# MCU042A_Engine.net
KiCad netlist of a schematic drawn in Altium Designer
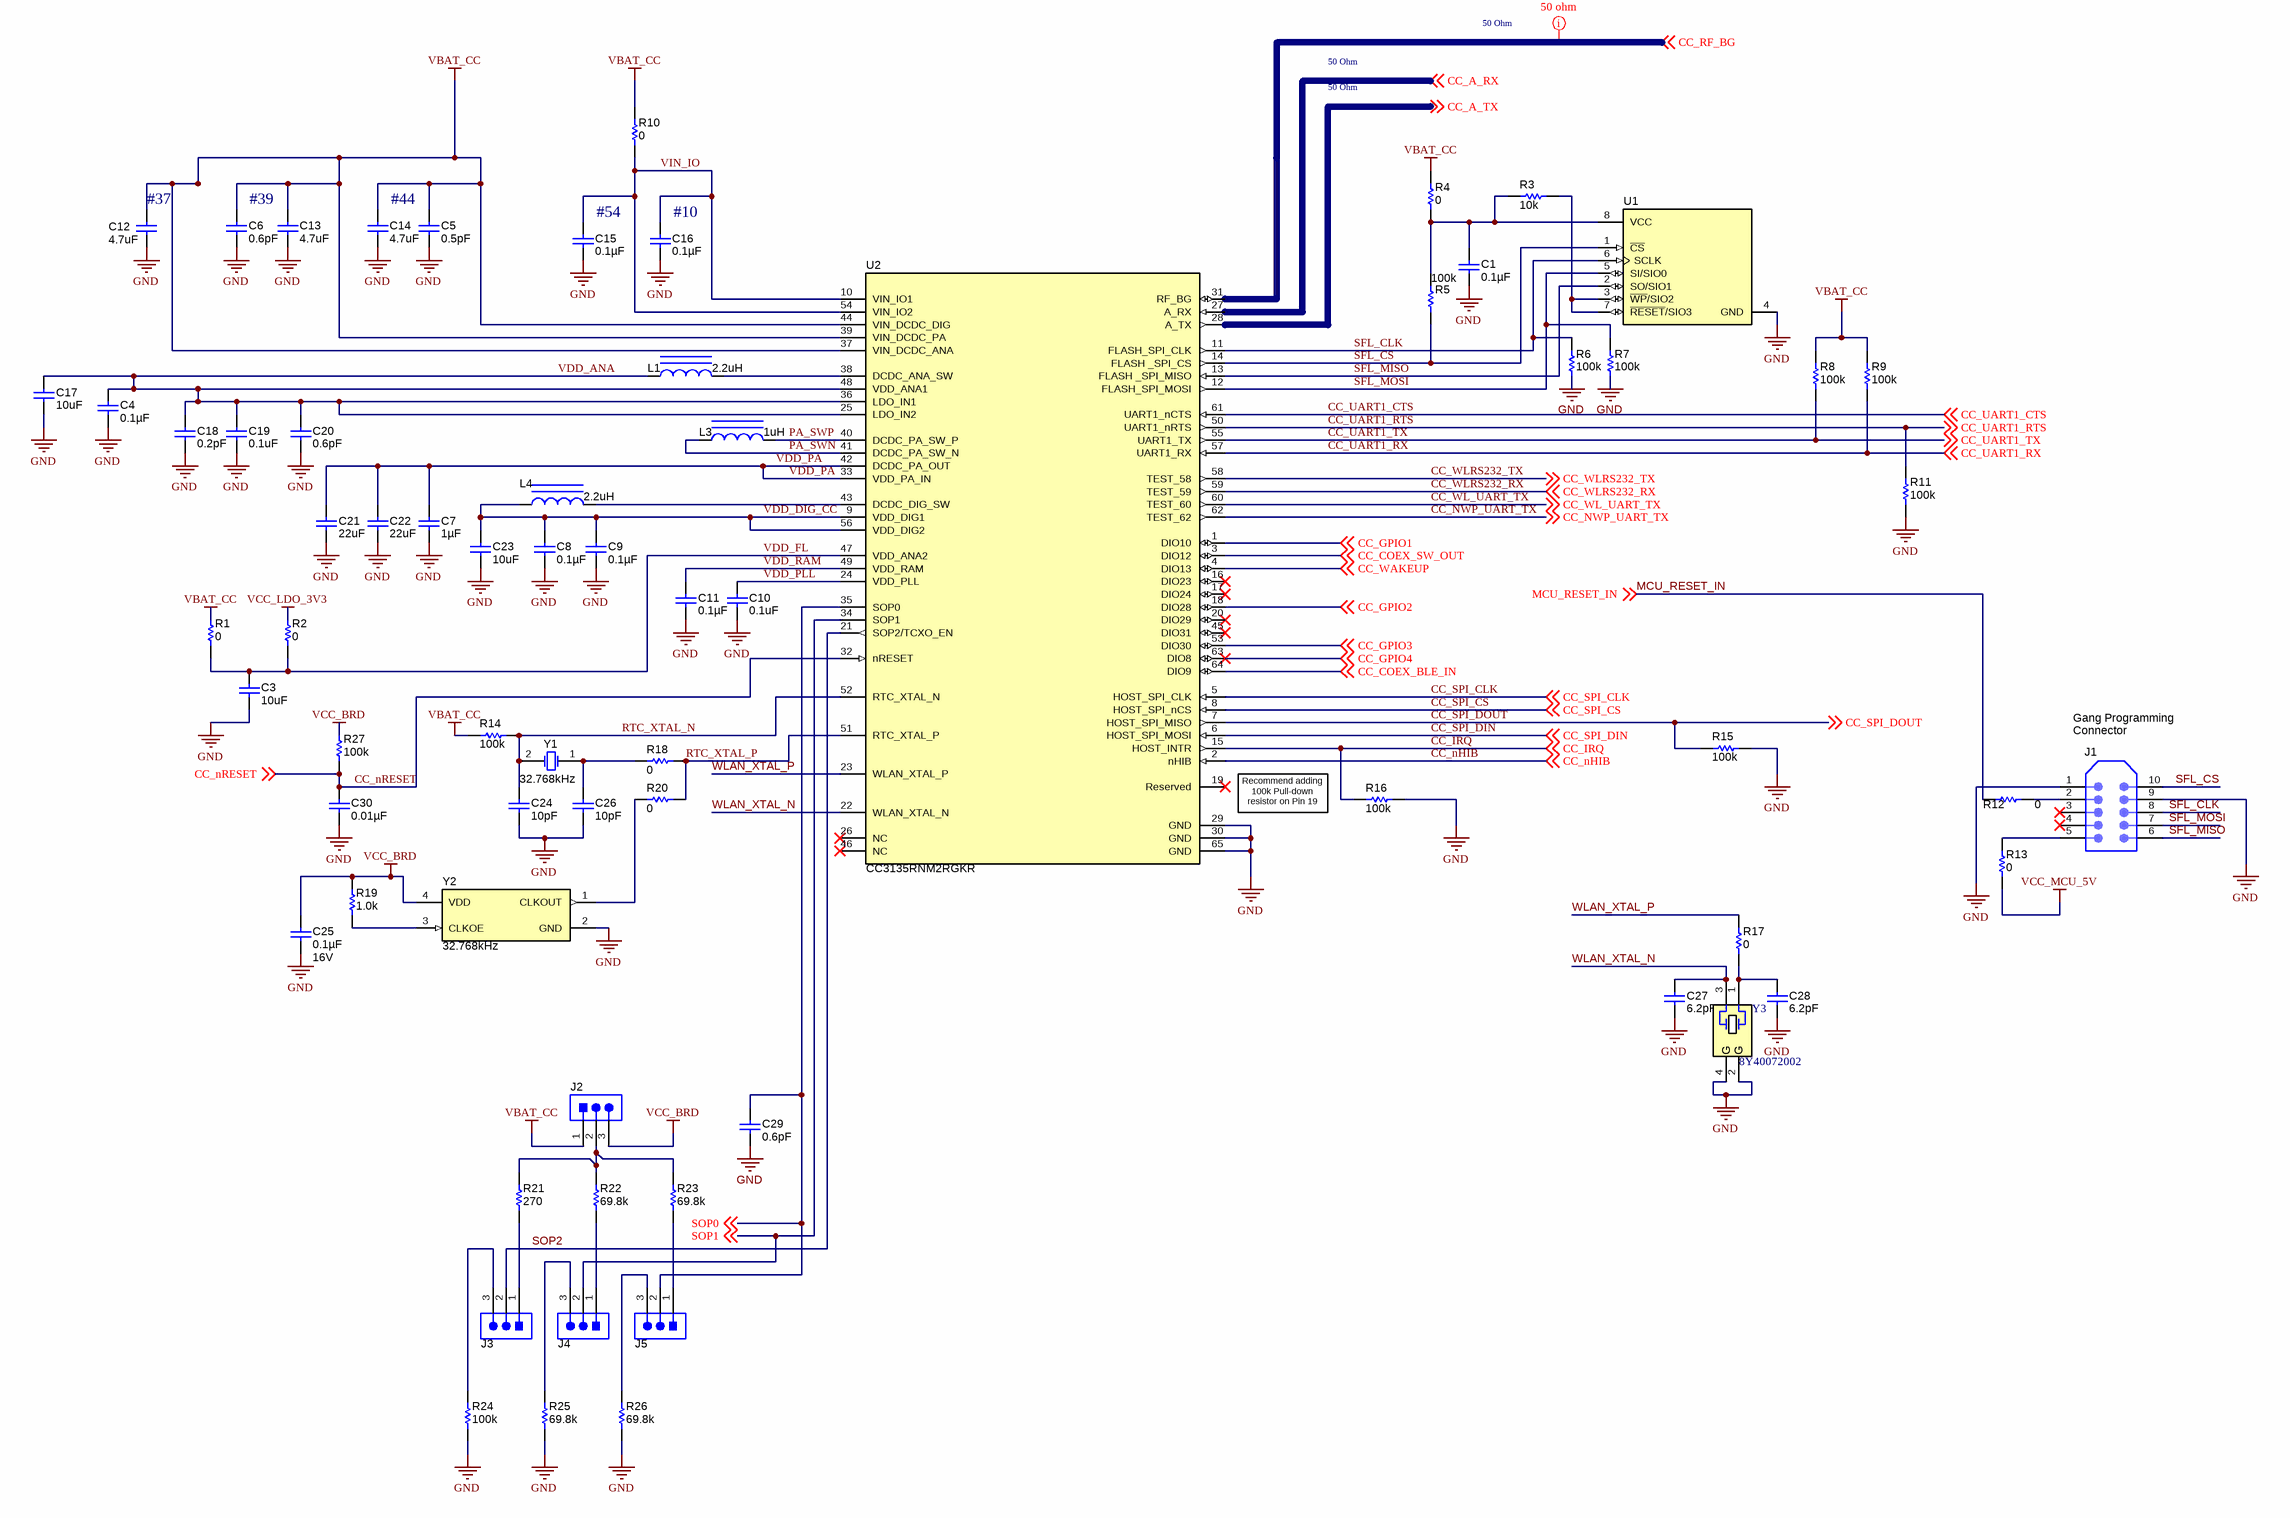
[diagram p0: MCU042A_Engine.SchDoc]

(export (version "E")
  (design (tool "Eeschema 10.0.6"))
  (components
    (comp (ref "C1")
      (value "CL05B104KO5NNNC")
      (footprint "0402")
      (description "CAP, CERM, 0.1 µF, 16 V,+/- 10%, X7R, 0402")
      (fields
        (field (name "VALUEDISPLAYED") "0.1µF")
        (field (name "MANUFACTURER") "Walsin")
        (field (name "ALTERNATE PARTNUMBER") "C1005X5R1A104K050BA")
      )
      (libsource (lib "Altium Vault - TI") (part "Capacitor"))
    )
    (comp (ref "C3")
      (value "CMP-0007303-5")
      (footprint "0603")
      (description "CAP, CERM, 10 uF, 6.3 V, +/- 20%, X5R, 0603")
      (fields
        (field (name "PARTNUMBER") "GRM188R60J106ME47D")
        (field (name "VALUEDISPLAYED") "10uF")
        (field (name "MANUFACTURER") "MuRata")
        (field (name "PUBLISHER") "Texas Instruments")
      )
      (libsource (lib "Altium Vault - TI") (part "CMP-0007303-5"))
    )
    (comp (ref "C4")
      (value "CL05B104KO5NNNC")
      (footprint "0402")
      (description "CAP, CERM, 0.1 µF, 16 V,+/- 10%, X7R, 0402")
      (fields
        (field (name "VALUEDISPLAYED") "0.1µF")
        (field (name "MANUFACTURER") "Walsin")
        (field (name "ALTERNATE PARTNUMBER") "C1005X5R1A104K050BA")
      )
      (libsource (lib "Altium Vault - TI") (part "Capacitor"))
    )
    (comp (ref "C5")
      (value "GJM0335C1ER50BB01D")
      (footprint "0201_033")
      (description "CAP, CERM, 0.5 pF, 25 V,+/- 20%, C0G/NP0, 0201")
      (fields (field (name "VALUEDISPLAYED") "0.5pF") (field (name "MANUFACTURER") "MuRata"))
      (libsource (lib "Altium Vault - TI") (part "Capacitor"))
    )
    (comp (ref "C6")
      (value "GJM0335C1ER60BB01D")
      (footprint "0201_033")
      (description "CAP, CERM, 0.6pF, 25 V,+/- 16%, C0G/NP0, 0201")
      (fields (field (name "VALUEDISPLAYED") "0.6pF") (field (name "MANUFACTURER") "MuRata"))
      (libsource (lib "Altium Vault - TI") (part "Capacitor"))
    )
    (comp (ref "C7")
      (value "CL05A105MP5NNNC")
      (footprint "0402")
      (description "CAP, CERM, 1 µF, 10 V,+/- 20%, X5R, 0402")
      (fields
        (field (name "VALUEDISPLAYED") "1µF")
        (field (name "MANUFACTURER") "Walsin")
        (field (name "ALTERNATE PARTNUMBER") "GRM155C81A105KA12D")
      )
      (libsource (lib "Altium Vault - TI") (part "Capacitor"))
    )
    (comp (ref "C8")
      (value "CL05B104KO5NNNC")
      (footprint "0402S")
      (description "CAP, CERM, 0.1 µF, 16 V,+/- 10%, X7R, 0402")
      (fields
        (field (name "VALUEDISPLAYED") "0.1µF")
        (field (name "MANUFACTURER") "Walsin")
        (field (name "ALTERNATE PARTNUMBER") "C1005X5R1A104K050BA")
      )
      (libsource (lib "Altium Vault - TI") (part "Capacitor"))
    )
    (comp (ref "C9")
      (value "CL05B104KO5NNNC")
      (footprint "0402S")
      (description "CAP, CERM, 0.1 µF, 16 V,+/- 10%, X7R, 0402")
      (fields
        (field (name "VALUEDISPLAYED") "0.1µF")
        (field (name "MANUFACTURER") "Walsin")
        (field (name "ALTERNATE PARTNUMBER") "C1005X5R1A104K050BA")
      )
      (libsource (lib "Altium Vault - TI") (part "Capacitor"))
    )
    (comp (ref "C10")
      (value "CMP-0009655-3")
      (footprint "0201")
      (description "CAP, CERM, 0.1 uF, 10 V, +/- 10%, X5R, 0201")
      (fields
        (field (name "PARTNUMBER") "CL03A104KP3NNNC")
        (field (name "VALUEDISPLAYED") "0.1uF")
        (field (name "MANUFACTURER") "Samsung Electro-Mechanics")
        (field (name "PUBLISHER") "Texas Instruments")
      )
      (libsource (lib "Altium Vault - TI") (part "Capacitor"))
    )
    (comp (ref "C11")
      (value "CL05B104KO5NNNC")
      (footprint "0402S")
      (description "CAP, CERM, 0.1 µF, 16 V,+/- 10%, X7R, 0402")
      (fields
        (field (name "VALUEDISPLAYED") "0.1µF")
        (field (name "MANUFACTURER") "Walsin")
        (field (name "ALTERNATE PARTNUMBER") "C1005X5R1A104K050BA")
      )
      (libsource (lib "Altium Vault - TI") (part "Capacitor"))
    )
    (comp (ref "C12")
      (value "CMP-0064972-2")
      (footprint "0402")
      (description "CAP, CERM, 4.7 uF, 6.3 V,+/- 20%, X6S, 0402")
      (fields
        (field (name "PARTNUMBER") "JMK105BC6475MV-F")
        (field (name "VALUEDISPLAYED") "4.7uF")
        (field (name "MANUFACTURER") "Taiyo Yuden")
        (field (name "PUBLISHER") "Texas Instruments")
      )
      (libsource (lib "Altium Vault - TI") (part "CMP-0064972-2"))
    )
    (comp (ref "C13")
      (value "CMP-0064972-2")
      (footprint "0402")
      (description "CAP, CERM, 4.7 uF, 6.3 V,+/- 20%, X6S, 0402")
      (fields
        (field (name "PARTNUMBER") "JMK105BC6475MV-F")
        (field (name "VALUEDISPLAYED") "4.7uF")
        (field (name "MANUFACTURER") "Taiyo Yuden")
        (field (name "PUBLISHER") "Texas Instruments")
      )
      (libsource (lib "Altium Vault - TI") (part "CMP-0064972-2"))
    )
    (comp (ref "C14")
      (value "CMP-0064972-2")
      (footprint "0402")
      (description "CAP, CERM, 4.7 uF, 6.3 V,+/- 20%, X6S, 0402")
      (fields
        (field (name "PARTNUMBER") "JMK105BC6475MV-F")
        (field (name "VALUEDISPLAYED") "4.7uF")
        (field (name "MANUFACTURER") "Taiyo Yuden")
        (field (name "PUBLISHER") "Texas Instruments")
      )
      (libsource (lib "Altium Vault - TI") (part "CMP-0064972-2"))
    )
    (comp (ref "C15")
      (value "CL05B104KO5NNNC")
      (footprint "0402S")
      (description "CAP, CERM, 0.1 µF, 16 V,+/- 10%, X7R, 0402")
      (fields
        (field (name "VALUEDISPLAYED") "0.1µF")
        (field (name "MANUFACTURER") "Walsin")
        (field (name "ALTERNATE PARTNUMBER") "C1005X5R1A104K050BA")
      )
      (libsource (lib "Altium Vault - TI") (part "Capacitor"))
    )
    (comp (ref "C16")
      (value "CL05B104KO5NNNC")
      (footprint "0402S")
      (description "CAP, CERM, 0.1 µF, 16 V,+/- 10%, X7R, 0402")
      (fields
        (field (name "VALUEDISPLAYED") "0.1µF")
        (field (name "MANUFACTURER") "Walsin")
        (field (name "ALTERNATE PARTNUMBER") "C1005X5R1A104K050BA")
      )
      (libsource (lib "Altium Vault - TI") (part "Capacitor"))
    )
    (comp (ref "C17")
      (value "CMP-0064953-4")
      (footprint "0603")
      (description "CAP, CERM, 10 uF, 10 V,+/- 20%, X6S, 0603")
      (fields
        (field (name "PARTNUMBER") "LMK107BC6106MA-T")
        (field (name "VALUEDISPLAYED") "10uF")
        (field (name "MANUFACTURER") "Taiyo Yuden")
        (field (name "PUBLISHER") "Texas Instruments")
      )
      (libsource (lib "Altium Vault - TI") (part "CMP-0064953-4"))
    )
    (comp (ref "C18")
      (value "GJM0335C1ER20BB01D")
      (footprint "0201_033")
      (description "CAP, CERM, 0.2pF, 25 V,+/- 50%, C0G/NP0, 0201")
      (fields (field (name "VALUEDISPLAYED") "0.2pF") (field (name "MANUFACTURER") "MuRata"))
      (libsource (lib "Altium Vault - TI") (part "Capacitor"))
    )
    (comp (ref "C19")
      (value "CL03A104KP3NNNC")
      (footprint "0201")
      (description "CAP, CERM, 0.1 uF, 10 V, +/- 10%, X5R, 0201")
      (fields
        (field (name "VALUEDISPLAYED") "0.1uF")
        (field (name "MANUFACTURER") "Samsung Electro-Mechanics")
        (field (name "PUBLISHER") "Texas Instruments")
      )
      (libsource (lib "Altium Vault - TI") (part "Capacitor"))
    )
    (comp (ref "C20")
      (value "GJM0335C1ER60BB01D")
      (footprint "0201_033")
      (description "CAP, CERM, 0.6pF, 25 V,+/- 16%, C0G/NP0, 0201")
      (fields (field (name "VALUEDISPLAYED") "0.6pF") (field (name "MANUFACTURER") "MuRata"))
      (libsource (lib "Altium Vault - TI") (part "Capacitor"))
    )
    (comp (ref "C21")
      (value "CMP-0064952-4")
      (footprint "0603")
      (description "CAP, CERM, 22 uF, 4 V,+/- 20%, X6S, 0603")
      (fields
        (field (name "PARTNUMBER") "GRM188C80G226ME15J")
        (field (name "VALUEDISPLAYED") "22uF")
        (field (name "MANUFACTURER") "MuRata")
        (field (name "PUBLISHER") "Texas Instruments")
      )
      (libsource (lib "Altium Vault - TI") (part "CMP-0064952-4"))
    )
    (comp (ref "C22")
      (value "CMP-0064952-4")
      (footprint "0603")
      (description "CAP, CERM, 22 uF, 4 V,+/- 20%, X6S, 0603")
      (fields
        (field (name "PARTNUMBER") "GRM188C80G226ME15J")
        (field (name "VALUEDISPLAYED") "22uF")
        (field (name "MANUFACTURER") "MuRata")
        (field (name "PUBLISHER") "Texas Instruments")
      )
      (libsource (lib "Altium Vault - TI") (part "CMP-0064952-4"))
    )
    (comp (ref "C23")
      (value "CMP-0064953-4")
      (footprint "0603")
      (description "CAP, CERM, 10 uF, 10 V,+/- 20%, X6S, 0603")
      (fields
        (field (name "PARTNUMBER") "LMK107BC6106MA-T")
        (field (name "VALUEDISPLAYED") "10uF")
        (field (name "MANUFACTURER") "Taiyo Yuden")
        (field (name "PUBLISHER") "Texas Instruments")
      )
      (libsource (lib "Altium Vault - TI") (part "CMP-0064953-4"))
    )
    (comp (ref "C24")
      (value "0402N100J500CT")
      (footprint "0402")
      (description "CAP, CERM, 10 pF, 50 V,+/- 5%, C0G/NP0, 0402")
      (fields
        (field (name "VALUEDISPLAYED") "10pF")
        (field (name "MANUFACTURER") "Walsin")
        (field (name "ALTERNATE PARTNUMBER") "GRM1555C1H100JA01D")
      )
      (libsource (lib "Altium Vault - TI") (part "Capacitor"))
    )
    (comp (ref "C25")
      (value "CL05B104KO5NNNC")
      (footprint "0402")
      (description "CAP, CERM, 0.1 µF, 16 V,+/- 10%, X7R, 0402")
      (fields
        (field (name "VALUEDISPLAYED") "0.1µF")
        (field (name "MANUFACTURER") "Walsin")
        (field (name "VDC_V") "16V")
      )
      (libsource (lib "Altium Vault - TI") (part "Capacitor"))
    )
    (comp (ref "C26")
      (value "0402N100J500CT")
      (footprint "0402")
      (description "CAP, CERM, 10 pF, 50 V,+/- 5%, C0G/NP0, 0402")
      (fields
        (field (name "VALUEDISPLAYED") "10pF")
        (field (name "MANUFACTURER") "Walsin")
        (field (name "ALTERNATE PARTNUMBER") "GRM1555C1H100JA01D")
      )
      (libsource (lib "Altium Vault - TI") (part "Capacitor"))
    )
    (comp (ref "C27")
      (value "0402N6R2C500CT")
      (footprint "0402")
      (description "CAP, CERM, 6.2 pF, 50 V,+/- 4%, C0G/NP0, 0402")
      (fields
        (field (name "VALUEDISPLAYED") "6.2pF")
        (field (name "MANUFACTURER") "Walsin")
        (field (name "ALTERNATE PARTNUMBER") "GRM1555C1H6R2CA1D")
      )
      (libsource (lib "Altium Vault - TI") (part "Capacitor"))
    )
    (comp (ref "C28")
      (value "0402N6R2C500CT")
      (footprint "0402")
      (description "CAP, CERM, 6.2 pF, 50 V,+/- 4%, C0G/NP0, 0402")
      (fields
        (field (name "VALUEDISPLAYED") "6.2pF")
        (field (name "MANUFACTURER") "Walsin")
        (field (name "ALTERNATE PARTNUMBER") "GRM1555C1H6R2CA1D")
      )
      (libsource (lib "Altium Vault - TI") (part "Capacitor"))
    )
    (comp (ref "C29")
      (value "GJM0335C1ER60BB01D")
      (footprint "0201_033")
      (description "CAP, CERM, 0.6pF, 25 V,+/- 16%, C0G/NP0, 0201")
      (fields (field (name "VALUEDISPLAYED") "0.6pF") (field (name "MANUFACTURER") "MuRata"))
      (libsource (lib "Altium Vault - TI") (part "Capacitor"))
    )
    (comp (ref "C30")
      (value "0402B103K500CT")
      (footprint "0402")
      (description "CAP, CERM, 0.01 µF, 50 V,+/- 10%, X7R, 0402")
      (fields
        (field (name "VALUEDISPLAYED") "0.01µF")
        (field (name "MANUFACTURER") "Walsin")
        (field (name "ALTERNATE PARTNUMBER") "GRM155R71E103KA01D")
      )
      (libsource (lib "Altium Vault - TI") (part "Capacitor"))
    )
    (comp (ref "J1")
      (value "TC2050-IDC-NL-FP")
      (footprint "Tag_TC2050-NL")
      (description "Footprint for Tag-Connect TC2050 No-Legs cables")
      (fields (field (name "MANUFACTURER") "Tag-Connect") (field (name "PUBLISHER") "Texas Instruments"))
      (libsource (lib "Altium Vault - TI") (part "CMP-0075101-1"))
    )
    (comp (ref "J2")
      (value "CMP-0054796-1")
      (footprint "WURTH_61300311121")
      (description "Header, 2.54 mm, 3x1, Gold, TH")
      (fields
        (field (name "PARTNUMBER") "61300311121")
        (field (name "MANUFACTURER") "Wurth Elektronik")
        (field (name "PUBLISHER") "Texas Instruments")
      )
      (libsource (lib "") (part "CMP-0054796-1_1"))
    )
    (comp (ref "J3")
      (value "CMP-0054796-1")
      (footprint "WURTH_61300311121")
      (description "Header, 2.54 mm, 3x1, Gold, TH")
      (fields
        (field (name "PARTNUMBER") "61300311121")
        (field (name "MANUFACTURER") "Wurth Elektronik")
        (field (name "PUBLISHER") "Texas Instruments")
      )
      (libsource (lib "Altium Vault - TI") (part "CMP-0054796-1"))
    )
    (comp (ref "J4")
      (value "CMP-0054796-1")
      (footprint "WURTH_61300311121")
      (description "Header, 2.54 mm, 3x1, Gold, TH")
      (fields
        (field (name "PARTNUMBER") "61300311121")
        (field (name "MANUFACTURER") "Wurth Elektronik")
        (field (name "PUBLISHER") "Texas Instruments")
      )
      (libsource (lib "Altium Vault - TI") (part "CMP-0054796-1"))
    )
    (comp (ref "J5")
      (value "CMP-0054796-1")
      (footprint "WURTH_61300311121")
      (description "Header, 2.54 mm, 3x1, Gold, TH")
      (fields
        (field (name "PARTNUMBER") "61300311121")
        (field (name "MANUFACTURER") "Wurth Elektronik")
        (field (name "PUBLISHER") "Texas Instruments")
      )
      (libsource (lib "Altium Vault - TI") (part "CMP-0054796-1"))
    )
    (comp (ref "L1")
      (value "CMP-0058761-1")
      (footprint "LQM2MPN_G0")
      (description "Inductor, Multilayer, Ferrite, 2.2 uH, 1.2 A, 0.11 ohm, SMD")
      (fields
        (field (name "PARTNUMBER") "LQM2MPN2R2NG0")
        (field (name "MANUFACTURER") "MuRata")
        (field (name "VALUEDISPLAYED") "2.2uH")
        (field (name "PUBLISHER") "Texas Instruments")
      )
      (libsource (lib "Altium Vault - TI") (part "Inductor_Iron"))
    )
    (comp (ref "L3")
      (value "CMP-0058750-1")
      (footprint "1008")
      (description "Inductor, Multilayer, Ferrite, 1 uH, 1.6 A, 0.055 ohm, SMD")
      (fields
        (field (name "PARTNUMBER") "LQM2HPN1R0MG0L")
        (field (name "MANUFACTURER") "MuRata")
        (field (name "VALUEDISPLAYED") "1uH")
        (field (name "PUBLISHER") "Texas Instruments")
      )
      (libsource (lib "Altium Vault - TI") (part "CMP-0058750-1"))
    )
    (comp (ref "L4")
      (value "CMP-0058761-1")
      (footprint "LQM2MPN_G0")
      (description "Inductor, Multilayer, Ferrite, 2.2 uH, 1.2 A, 0.11 ohm, SMD")
      (fields
        (field (name "PARTNUMBER") "LQM2MPN2R2NG0")
        (field (name "MANUFACTURER") "MuRata")
        (field (name "VALUEDISPLAYED") "2.2uH")
        (field (name "PUBLISHER") "Texas Instruments")
      )
      (libsource (lib "Altium Vault - TI") (part "Inductor_Iron"))
    )
    (comp (ref "R1")
      (value "CMP-0025885-3")
      (footprint "0603")
      (description "RES, 0, 5%, 0.1 W, 0603")
      (fields
        (field (name "PARTNUMBER") "RC0603JR-070RL")
        (field (name "VALUEDISPLAYED") "0")
        (field (name "MANUFACTURER") "Yageo America")
        (field (name "PUBLISHER") "Texas Instruments")
      )
      (libsource (lib "Altium Vault - TI") (part "Resistor"))
    )
    (comp (ref "R2")
      (value "CMP-0025885-3")
      (footprint "0603")
      (description "RES, 0, 5%, 0.1 W, 0603")
      (fields
        (field (name "PARTNUMBER") "RC0603JR-070RL")
        (field (name "VALUEDISPLAYED") "0")
        (field (name "MANUFACTURER") "Yageo America")
        (field (name "PUBLISHER") "Texas Instruments")
      )
      (libsource (lib "Altium Vault - TI") (part "Resistor"))
    )
    (comp (ref "R3")
      (value "CMP-0026825-5")
      (footprint "0402")
      (description "RES, 10 k, 5%, 0.063 W, AEC-Q200 Grade 0, 0402")
      (fields
        (field (name "PARTNUMBER") "CRCW040210K0JNED")
        (field (name "VALUEDISPLAYED") "10k")
        (field (name "MANUFACTURER") "Vishay-Dale")
      )
      (libsource (lib "Altium Vault - TI") (part "Resistor"))
    )
    (comp (ref "R4")
      (value "CMP-0025885-3")
      (footprint "0603")
      (description "RES, 0, 5%, 0.1 W, 0603")
      (fields
        (field (name "PARTNUMBER") "RC0603JR-070RL")
        (field (name "VALUEDISPLAYED") "0")
        (field (name "MANUFACTURER") "Yageo America")
        (field (name "PUBLISHER") "Texas Instruments")
      )
      (libsource (lib "Altium Vault - TI") (part "Resistor"))
    )
    (comp (ref "R5")
      (value "CMP-0026823-3")
      (footprint "0402")
      (description "RES, 100 k, 5%, 0.063 W, AEC-Q200 Grade 0, 0402")
      (fields
        (field (name "PARTNUMBER") "CRCW0402100KJNED")
        (field (name "VALUEDISPLAYED") "100k")
        (field (name "MANUFACTURER") "Vishay-Dale")
      )
      (libsource (lib "Altium Vault - TI") (part "Resistor"))
    )
    (comp (ref "R6")
      (value "CMP-0026823-3")
      (footprint "0402S")
      (description "RES, 100 k, 5%, 0.063 W, AEC-Q200 Grade 0, 0402")
      (fields
        (field (name "PARTNUMBER") "CRCW0402100KJNED")
        (field (name "VALUEDISPLAYED") "100k")
        (field (name "MANUFACTURER") "Vishay-Dale")
      )
      (libsource (lib "Altium Vault - TI") (part "CMP-0026823-3"))
    )
    (comp (ref "R7")
      (value "CMP-0026823-3")
      (footprint "0402S")
      (description "RES, 100 k, 5%, 0.063 W, AEC-Q200 Grade 0, 0402")
      (fields
        (field (name "PARTNUMBER") "CRCW0402100KJNED")
        (field (name "VALUEDISPLAYED") "100k")
        (field (name "MANUFACTURER") "Vishay-Dale")
      )
      (libsource (lib "Altium Vault - TI") (part "CMP-0026823-3"))
    )
    (comp (ref "R8")
      (value "CMP-0026823-3")
      (footprint "0402")
      (description "RES, 100 k, 5%, 0.063 W, AEC-Q200 Grade 0, 0402")
      (fields
        (field (name "PARTNUMBER") "CRCW0402100KJNED")
        (field (name "VALUEDISPLAYED") "100k")
        (field (name "MANUFACTURER") "Vishay-Dale")
      )
      (libsource (lib "Altium Vault - TI") (part "Resistor"))
    )
    (comp (ref "R9")
      (value "CMP-0026823-3")
      (footprint "0402")
      (description "RES, 100 k, 5%, 0.063 W, AEC-Q200 Grade 0, 0402")
      (fields
        (field (name "PARTNUMBER") "CRCW0402100KJNED")
        (field (name "VALUEDISPLAYED") "100k")
        (field (name "MANUFACTURER") "Vishay-Dale")
      )
      (libsource (lib "Altium Vault - TI") (part "Resistor"))
    )
    (comp (ref "R10")
      (value "CMP-0025885-3")
      (footprint "0603")
      (description "RES, 0, 5%, 0.1 W, 0603")
      (fields
        (field (name "PARTNUMBER") "RC0603JR-070RL")
        (field (name "VALUEDISPLAYED") "0")
        (field (name "MANUFACTURER") "Yageo America")
        (field (name "PUBLISHER") "Texas Instruments")
      )
      (libsource (lib "Altium Vault - TI") (part "Resistor"))
    )
    (comp (ref "R11")
      (value "CMP-0026823-3")
      (footprint "0402")
      (description "RES, 100 k, 5%, 0.063 W, AEC-Q200 Grade 0, 0402")
      (fields
        (field (name "PARTNUMBER") "CRCW0402100KJNED")
        (field (name "VALUEDISPLAYED") "100k")
        (field (name "MANUFACTURER") "Vishay-Dale")
      )
      (libsource (lib "Altium Vault - TI") (part "Resistor"))
    )
    (comp (ref "R12")
      (value "CMP-0026992-2")
      (footprint "0402")
      (description "RES, 0, 5%, 0.063 W, 0402")
      (fields
        (field (name "PARTNUMBER") "ERJ-2GE0R00X")
        (field (name "VALUEDISPLAYED") "0")
        (field (name "MANUFACTURER") "Panasonic")
        (field (name "PUBLISHER") "Texas Instruments")
      )
      (libsource (lib "Altium Vault - TI") (part "Resistor"))
    )
    (comp (ref "R13")
      (value "CMP-0026992-2")
      (footprint "0402")
      (description "RES, 0, 5%, 0.063 W, 0402")
      (fields
        (field (name "PARTNUMBER") "ERJ-2GE0R00X")
        (field (name "VALUEDISPLAYED") "0")
        (field (name "MANUFACTURER") "Panasonic")
        (field (name "PUBLISHER") "Texas Instruments")
      )
      (libsource (lib "Altium Vault - TI") (part "Resistor"))
    )
    (comp (ref "R14")
      (value "CMP-0026823-3")
      (footprint "0402")
      (description "RES, 100 k, 5%, 0.063 W, AEC-Q200 Grade 0, 0402")
      (fields
        (field (name "PARTNUMBER") "CRCW0402100KJNED")
        (field (name "VALUEDISPLAYED") "100k")
        (field (name "MANUFACTURER") "Vishay-Dale")
      )
      (libsource (lib "Altium Vault - TI") (part "Resistor"))
    )
    (comp (ref "R15")
      (value "CMP-0026823-3")
      (footprint "0402")
      (description "RES, 100 k, 5%, 0.063 W, AEC-Q200 Grade 0, 0402")
      (fields
        (field (name "PARTNUMBER") "CRCW0402100KJNED")
        (field (name "VALUEDISPLAYED") "100k")
        (field (name "MANUFACTURER") "Vishay-Dale")
      )
      (libsource (lib "Altium Vault - TI") (part "Resistor"))
    )
    (comp (ref "R16")
      (value "CMP-0026823-3")
      (footprint "0402")
      (description "RES, 100 k, 5%, 0.063 W, AEC-Q200 Grade 0, 0402")
      (fields
        (field (name "PARTNUMBER") "CRCW0402100KJNED")
        (field (name "VALUEDISPLAYED") "100k")
        (field (name "MANUFACTURER") "Vishay-Dale")
      )
      (libsource (lib "Altium Vault - TI") (part "Resistor"))
    )
    (comp (ref "R17")
      (value "CMP-0026992-2")
      (footprint "0402")
      (description "RES, 0, 5%, 0.063 W, 0402")
      (fields
        (field (name "PARTNUMBER") "ERJ-2GE0R00X")
        (field (name "VALUEDISPLAYED") "0")
        (field (name "MANUFACTURER") "Panasonic")
        (field (name "PUBLISHER") "Texas Instruments")
      )
      (libsource (lib "Altium Vault - TI") (part "Resistor"))
    )
    (comp (ref "R18")
      (value "CMP-0026992-2")
      (footprint "0402")
      (description "RES, 0, 5%, 0.063 W, 0402")
      (fields
        (field (name "PARTNUMBER") "ERJ-2GE0R00X")
        (field (name "VALUEDISPLAYED") "0")
        (field (name "MANUFACTURER") "Panasonic")
        (field (name "PUBLISHER") "Texas Instruments")
      )
      (libsource (lib "Altium Vault - TI") (part "Resistor"))
    )
    (comp (ref "R19")
      (value "CMP-0026852-3")
      (footprint "0402")
      (description "RES, 1.0 k, 5%, 0.063 W, AEC-Q200 Grade 0, 0402")
      (fields
        (field (name "PARTNUMBER") "CRCW04021K00JNED")
        (field (name "VALUEDISPLAYED") "1.0k")
        (field (name "MANUFACTURER") "Vishay-Dale")
      )
      (libsource (lib "Altium Vault - TI") (part "CMP-0026852-3"))
    )
    (comp (ref "R20")
      (value "CMP-0026992-2")
      (footprint "0402")
      (description "RES, 0, 5%, 0.063 W, 0402")
      (fields
        (field (name "PARTNUMBER") "ERJ-2GE0R00X")
        (field (name "VALUEDISPLAYED") "0")
        (field (name "MANUFACTURER") "Panasonic")
        (field (name "PUBLISHER") "Texas Instruments")
      )
      (libsource (lib "Altium Vault - TI") (part "Resistor"))
    )
    (comp (ref "R21")
      (value "CMP-0026886-3")
      (footprint "0402")
      (description "RES, 270, 5%, 0.063 W, AEC-Q200 Grade 0, 0402")
      (fields
        (field (name "PARTNUMBER") "CRCW0402270RJNED")
        (field (name "VALUEDISPLAYED") "270")
        (field (name "MANUFACTURER") "Vishay-Dale")
      )
      (libsource (lib "Altium Vault - TI") (part "CMP-0026886-3"))
    )
    (comp (ref "R22")
      (value "CMP-0026510-2")
      (footprint "0402")
      (description "RES, 69.8 k, 1%, 0.063 W, AEC-Q200 Grade 0, 0402")
      (fields
        (field (name "PARTNUMBER") "CRCW040269K8FKED")
        (field (name "VALUEDISPLAYED") "69.8k")
        (field (name "MANUFACTURER") "Vishay-Dale")
      )
      (libsource (lib "Altium Vault - TI") (part "Resistor"))
    )
    (comp (ref "R23")
      (value "CMP-0026510-2")
      (footprint "0402")
      (description "RES, 69.8 k, 1%, 0.063 W, AEC-Q200 Grade 0, 0402")
      (fields
        (field (name "PARTNUMBER") "CRCW040269K8FKED")
        (field (name "VALUEDISPLAYED") "69.8k")
        (field (name "MANUFACTURER") "Vishay-Dale")
      )
      (libsource (lib "Altium Vault - TI") (part "Resistor"))
    )
    (comp (ref "R24")
      (value "CMP-0026823-3")
      (footprint "0402")
      (description "RES, 100 k, 5%, 0.063 W, AEC-Q200 Grade 0, 0402")
      (fields
        (field (name "PARTNUMBER") "CRCW0402100KJNED")
        (field (name "VALUEDISPLAYED") "100k")
        (field (name "MANUFACTURER") "Vishay-Dale")
      )
      (libsource (lib "Altium Vault - TI") (part "Resistor"))
    )
    (comp (ref "R25")
      (value "CMP-0026510-2")
      (footprint "0402")
      (description "RES, 69.8 k, 1%, 0.063 W, AEC-Q200 Grade 0, 0402")
      (fields
        (field (name "PARTNUMBER") "CRCW040269K8FKED")
        (field (name "VALUEDISPLAYED") "69.8k")
        (field (name "MANUFACTURER") "Vishay-Dale")
      )
      (libsource (lib "Altium Vault - TI") (part "Resistor"))
    )
    (comp (ref "R26")
      (value "CMP-0026510-2")
      (footprint "0402")
      (description "RES, 69.8 k, 1%, 0.063 W, AEC-Q200 Grade 0, 0402")
      (fields
        (field (name "PARTNUMBER") "CRCW040269K8FKED")
        (field (name "VALUEDISPLAYED") "69.8k")
        (field (name "MANUFACTURER") "Vishay-Dale")
      )
      (libsource (lib "Altium Vault - TI") (part "Resistor"))
    )
    (comp (ref "R27")
      (value "CMP-0026823-3")
      (footprint "0402")
      (description "RES, 100 k, 5%, 0.063 W, AEC-Q200 Grade 0, 0402")
      (fields
        (field (name "PARTNUMBER") "CRCW0402100KJNED")
        (field (name "VALUEDISPLAYED") "100k")
        (field (name "MANUFACTURER") "Vishay-Dale")
      )
      (libsource (lib "Altium Vault - TI") (part "Resistor"))
    )
    (comp (ref "U1")
      (value "CMP-0004904-1")
      (footprint "SOP-8_150MIL")
      (description "ULTRA LOW POWER, 16M-BIT [x 1/x 2/x 4] CMOS MXSMIO(SERIAL MULTI I/O) FLASH MEMORY, SOP-8")
      (fields
        (field (name "PARTNUMBER") "MX25R1635FM1IL0")
        (field (name "MANUFACTURER") "Macronix International Co., LTD")
        (field (name "PUBLISHER") "Texas Instruments")
      )
      (libsource (lib "Altium Vault - TI") (part "CMP-0004904-1"))
    )
    (comp (ref "U2")
      (value "CC3135RNM2RGKR")
      (footprint "RGK0064B")
      (description "CC3135, RGK0064B (VQFN-64)")
      (fields
        (field (name "ALTERNATE PARTNUMBER") "CC3135RNM2RGKT")
        (field (name "MANUFACTURER") "Texas Instruments")
        (field (name "PARTNUMBER") "CC3135RNM2RGKR")
      )
      (libsource (lib "Altium Vault - TI") (part "CC3135"))
    )
    (comp (ref "Y1")
      (value "CMP-0004575-3")
      (footprint "XTAL_ABS07")
      (description "CRYSTAL, 32.768KHz, 9PF, SMD")
      (fields
        (field (name "PARTNUMBER") "ABS07-32.768KHZ-9-T")
        (field (name "MANUFACTURER") "Abracon Corporation")
        (field (name "FREQUENCY_FIXED") "32.768kHz")
      )
      (libsource (lib "Altium Vault - TI") (part "CMP-0004575-3"))
    )
    (comp (ref "Y2")
      (value "CMP-0004716-3")
      (footprint "MC_OV-7604-C7")
      (description "Low Power Clock Oscillator, 32.768 kHz, SMD")
      (fields
        (field (name "PARTNUMBER") "OV-7604-C7")
        (field (name "MANUFACTURER") "Micro Crystal AG")
        (field (name "FREQUENCY_FIXED") "32.768kHz")
      )
      (libsource (lib "Altium Vault - TI") (part "CMP-0004716-3"))
    )
    (comp (ref "Y3")
      (value "8Y40072002")
      (footprint "TXC_8Y")
      (description "Crystal, 40 MHz, 8 pF, SMD")
      (fields
        (field (name "MANUFACTURER") "TXC Corporation")
        (field (name "ALTERNATE PARTNUMBER") "Direct from MFR")
        (field (name "PUBLISHER") "Texas Instruments")
      )
      (libsource (lib "Altium Vault - TI") (part "CMP-0077111-2"))
    )
  )
  (nets
    (net (code "1") (name "/PA_SWN") (class "Default")
      (node (ref "L3") (pin "1") (pinfunction "1_1") (pintype "passive"))
      (node (ref "U2") (pin "41") (pinfunction "DCDC_PA_SW_N_41") (pintype "power_in"))
    )
    (net (code "2") (name "/PA_SWP") (class "Default")
      (node (ref "L3") (pin "2") (pinfunction "2_2") (pintype "passive"))
      (node (ref "U2") (pin "40") (pinfunction "DCDC_PA_SW_P_40") (pintype "power_in"))
    )
    (net (code "3") (name "/RTC_XTAL_N") (class "Default")
      (node (ref "C24") (pin "1") (pinfunction "1_1") (pintype "passive"))
      (node (ref "R14") (pin "2") (pinfunction "2_2") (pintype "passive"))
      (node (ref "U2") (pin "52") (pinfunction "RTC_XTAL_N_52") (pintype "passive"))
      (node (ref "Y1") (pin "2") (pinfunction "OSC2_2") (pintype "passive"))
    )
    (net (code "4") (name "/RTC_XTAL_P") (class "Default")
      (node (ref "R18") (pin "2") (pinfunction "2_2") (pintype "passive"))
      (node (ref "R20") (pin "2") (pinfunction "2_2") (pintype "passive"))
      (node (ref "U2") (pin "51") (pinfunction "RTC_XTAL_P_51") (pintype "passive"))
    )
    (net (code "5") (name "/SFL_CLK") (class "Default")
      (node (ref "J1") (pin "8") (pinfunction "8_8") (pintype "passive"))
      (node (ref "R6") (pin "2") (pinfunction "2_2") (pintype "passive"))
      (node (ref "U1") (pin "6") (pinfunction "SCLK_6") (pintype "input"))
      (node (ref "U2") (pin "11") (pinfunction "FLASH_SPI_CLK_11") (pintype "output"))
    )
    (net (code "6") (name "/SFL_CS") (class "Default")
      (node (ref "J1") (pin "10") (pinfunction "10_10") (pintype "passive"))
      (node (ref "R5") (pin "2") (pinfunction "2_2") (pintype "passive"))
      (node (ref "U1") (pin "1") (pinfunction "CS_1") (pintype "input"))
      (node (ref "U2") (pin "14") (pinfunction "FLASH__SPI_CS_14") (pintype "output"))
    )
    (net (code "7") (name "/SFL_MISO") (class "Default")
      (node (ref "J1") (pin "6") (pinfunction "6_6") (pintype "passive"))
      (node (ref "U1") (pin "2") (pinfunction "SO/SIO1_2") (pintype "bidirectional"))
      (node (ref "U2") (pin "13") (pinfunction "FLASH__SPI_MISO_13") (pintype "input"))
    )
    (net (code "8") (name "/SFL_MOSI") (class "Default")
      (node (ref "J1") (pin "7") (pinfunction "7_7") (pintype "passive"))
      (node (ref "R7") (pin "2") (pinfunction "2_2") (pintype "passive"))
      (node (ref "U1") (pin "5") (pinfunction "SI/SIO0_5") (pintype "bidirectional"))
      (node (ref "U2") (pin "12") (pinfunction "FLASH_SPI_MOSI_12") (pintype "output"))
    )
    (net (code "9") (name "/SOP2") (class "Default")
      (node (ref "J3") (pin "2") (pinfunction "2_2") (pintype "passive"))
      (node (ref "U2") (pin "21") (pinfunction "SOP2/TCXO_EN_21") (pintype "output"))
    )
    (net (code "10") (name "/VDD_ANA") (class "Default")
      (node (ref "C17") (pin "1") (pinfunction "1_1") (pintype "passive"))
      (node (ref "C18") (pin "1") (pinfunction "1_1") (pintype "passive"))
      (node (ref "C19") (pin "1") (pinfunction "1_1") (pintype "passive"))
      (node (ref "C20") (pin "1") (pinfunction "1_1") (pintype "passive"))
      (node (ref "C4") (pin "1") (pinfunction "1_1") (pintype "passive"))
      (node (ref "L1") (pin "1") (pinfunction "1_1") (pintype "passive"))
      (node (ref "U2") (pin "25") (pinfunction "LDO_IN2_25") (pintype "power_in"))
      (node (ref "U2") (pin "36") (pinfunction "LDO_IN1_36") (pintype "power_in"))
      (node (ref "U2") (pin "48") (pinfunction "VDD_ANA1_48") (pintype "power_in"))
    )
    (net (code "11") (name "/VDD_DIG_CC") (class "Default")
      (node (ref "C23") (pin "1") (pinfunction "1_1") (pintype "passive"))
      (node (ref "C8") (pin "1") (pinfunction "1_1") (pintype "passive"))
      (node (ref "C9") (pin "1") (pinfunction "1_1") (pintype "passive"))
      (node (ref "L4") (pin "1") (pinfunction "1_1") (pintype "passive"))
      (node (ref "U2") (pin "56") (pinfunction "VDD_DIG2_56") (pintype "power_in"))
      (node (ref "U2") (pin "9") (pinfunction "VDD_DIG1_9") (pintype "power_in"))
    )
    (net (code "12") (name "/VDD_FL") (class "Default")
      (node (ref "C3") (pin "1") (pinfunction "1_1") (pintype "passive"))
      (node (ref "R1") (pin "1") (pinfunction "1_1") (pintype "passive"))
      (node (ref "R2") (pin "1") (pinfunction "1_1") (pintype "passive"))
      (node (ref "U2") (pin "47") (pinfunction "VDD_ANA2_47") (pintype "power_in"))
    )
    (net (code "13") (name "/VDD_PA") (class "Default")
      (node (ref "C21") (pin "1") (pinfunction "1_1") (pintype "passive"))
      (node (ref "C22") (pin "1") (pinfunction "1_1") (pintype "passive"))
      (node (ref "C7") (pin "1") (pinfunction "1_1") (pintype "passive"))
      (node (ref "U2") (pin "33") (pinfunction "VDD_PA_IN_33") (pintype "power_in"))
      (node (ref "U2") (pin "42") (pinfunction "DCDC_PA_OUT_42") (pintype "power_in"))
    )
    (net (code "14") (name "/VDD_PLL") (class "Default")
      (node (ref "C10") (pin "1") (pinfunction "1_1") (pintype "passive"))
      (node (ref "U2") (pin "24") (pinfunction "VDD_PLL_24") (pintype "power_in"))
    )
    (net (code "15") (name "/VDD_RAM") (class "Default")
      (node (ref "C11") (pin "1") (pinfunction "1_1") (pintype "passive"))
      (node (ref "U2") (pin "49") (pinfunction "VDD_RAM_49") (pintype "power_in"))
    )
    (net (code "16") (name "/VIN_IO") (class "Default")
      (node (ref "C15") (pin "1") (pinfunction "1_1") (pintype "passive"))
      (node (ref "C16") (pin "1") (pinfunction "1_1") (pintype "passive"))
      (node (ref "R10") (pin "1") (pinfunction "1_1") (pintype "passive"))
      (node (ref "U2") (pin "10") (pinfunction "VIN_IO1_10") (pintype "power_in"))
      (node (ref "U2") (pin "54") (pinfunction "VIN_IO2_54") (pintype "power_in"))
    )
    (net (code "17") (name "/WLAN_XTAL_N") (class "Default")
      (node (ref "C27") (pin "1") (pinfunction "1_1") (pintype "passive"))
      (node (ref "U2") (pin "22") (pinfunction "WLAN_XTAL_N_22") (pintype "passive"))
      (node (ref "Y3") (pin "3") (pinfunction "3_3") (pintype "passive"))
    )
    (net (code "18") (name "/WLAN_XTAL_P") (class "Default")
      (node (ref "R17") (pin "2") (pinfunction "2_2") (pintype "passive"))
      (node (ref "U2") (pin "23") (pinfunction "WLAN_XTAL_P_23") (pintype "passive"))
    )
    (net (code "19") (name "CC_A_RX") (class "Default")
      (node (ref "U2") (pin "27") (pinfunction "A_RX_27") (pintype "input"))
    )
    (net (code "20") (name "CC_A_TX") (class "Default")
      (node (ref "U2") (pin "28") (pinfunction "A_TX_28") (pintype "output"))
    )
    (net (code "21") (name "CC_COEX_BLE_IN") (class "Default")
      (node (ref "U2") (pin "64") (pinfunction "DIO9_64") (pintype "bidirectional"))
    )
    (net (code "22") (name "CC_COEX_SW_OUT") (class "Default")
      (node (ref "U2") (pin "3") (pinfunction "DIO12_3") (pintype "bidirectional"))
    )
    (net (code "23") (name "CC_GPIO1") (class "Default")
      (node (ref "U2") (pin "1") (pinfunction "DIO10_1") (pintype "bidirectional"))
    )
    (net (code "24") (name "CC_GPIO2") (class "Default")
      (node (ref "U2") (pin "18") (pinfunction "DIO28_18") (pintype "bidirectional"))
    )
    (net (code "25") (name "CC_GPIO3") (class "Default")
      (node (ref "U2") (pin "53") (pinfunction "DIO30_53") (pintype "bidirectional"))
    )
    (net (code "26") (name "CC_GPIO4") (class "Default")
      (node (ref "U2") (pin "63") (pinfunction "DIO8_63") (pintype "bidirectional"))
    )
    (net (code "27") (name "CC_IRQ") (class "Default")
      (node (ref "R16") (pin "1") (pinfunction "1_1") (pintype "passive"))
      (node (ref "U2") (pin "15") (pinfunction "HOST_INTR_15") (pintype "output"))
    )
    (net (code "28") (name "CC_NWP_UART_TX") (class "Default")
      (node (ref "U2") (pin "62") (pinfunction "TEST_62_62") (pintype "output"))
    )
    (net (code "29") (name "CC_RF_BG") (class "Default")
      (node (ref "U2") (pin "31") (pinfunction "RF_BG_31") (pintype "bidirectional"))
    )
    (net (code "30") (name "CC_SPI_CLK") (class "Default")
      (node (ref "U2") (pin "5") (pinfunction "HOST_SPI_CLK_5") (pintype "input"))
    )
    (net (code "31") (name "CC_SPI_CS") (class "Default")
      (node (ref "U2") (pin "8") (pinfunction "HOST_SPI_nCS_8") (pintype "input"))
    )
    (net (code "32") (name "CC_SPI_DIN") (class "Default")
      (node (ref "U2") (pin "6") (pinfunction "HOST_SPI_MOSI_6") (pintype "input"))
    )
    (net (code "33") (name "CC_SPI_DOUT") (class "Default")
      (node (ref "R15") (pin "1") (pinfunction "1_1") (pintype "passive"))
      (node (ref "U2") (pin "7") (pinfunction "HOST_SPI_MISO_7") (pintype "output"))
    )
    (net (code "34") (name "CC_UART1_CTS") (class "Default")
      (node (ref "U2") (pin "61") (pinfunction "UART1_nCTS_61") (pintype "input"))
    )
    (net (code "35") (name "CC_UART1_RTS") (class "Default")
      (node (ref "R11") (pin "1") (pinfunction "1_1") (pintype "passive"))
      (node (ref "U2") (pin "50") (pinfunction "UART1_nRTS_50") (pintype "output"))
    )
    (net (code "36") (name "CC_UART1_RX") (class "Default")
      (node (ref "R9") (pin "2") (pinfunction "2_2") (pintype "passive"))
      (node (ref "U2") (pin "57") (pinfunction "UART1_RX_57") (pintype "input"))
    )
    (net (code "37") (name "CC_UART1_TX") (class "Default")
      (node (ref "R8") (pin "2") (pinfunction "2_2") (pintype "passive"))
      (node (ref "U2") (pin "55") (pinfunction "UART1_TX_55") (pintype "output"))
    )
    (net (code "38") (name "CC_WAKEUP") (class "Default")
      (node (ref "U2") (pin "4") (pinfunction "DIO13_4") (pintype "bidirectional"))
    )
    (net (code "39") (name "CC_WLRS232_RX") (class "Default")
      (node (ref "U2") (pin "59") (pinfunction "TEST_59_59") (pintype "output"))
    )
    (net (code "40") (name "CC_WLRS232_TX") (class "Default")
      (node (ref "U2") (pin "58") (pinfunction "TEST_58_58") (pintype "output"))
    )
    (net (code "41") (name "CC_WL_UART_TX") (class "Default")
      (node (ref "U2") (pin "60") (pinfunction "TEST_60_60") (pintype "output"))
    )
    (net (code "42") (name "CC_nHIB") (class "Default")
      (node (ref "U2") (pin "2") (pinfunction "nHIB_2") (pintype "input"))
    )
    (net (code "43") (name "CC_nRESET") (class "Default")
      (node (ref "C30") (pin "1") (pinfunction "1_1") (pintype "passive"))
      (node (ref "R27") (pin "2") (pinfunction "2_2") (pintype "passive"))
      (node (ref "U2") (pin "32") (pinfunction "nRESET_32") (pintype "input"))
    )
    (net (code "44") (name "GND") (class "Default")
      (node (ref "C1") (pin "2") (pinfunction "2_2") (pintype "passive"))
      (node (ref "C10") (pin "2") (pinfunction "2_2") (pintype "passive"))
      (node (ref "C11") (pin "2") (pinfunction "2_2") (pintype "passive"))
      (node (ref "C12") (pin "2") (pinfunction "2_2") (pintype "passive"))
      (node (ref "C13") (pin "2") (pinfunction "2_2") (pintype "passive"))
      (node (ref "C14") (pin "2") (pinfunction "2_2") (pintype "passive"))
      (node (ref "C15") (pin "2") (pinfunction "2_2") (pintype "passive"))
      (node (ref "C16") (pin "2") (pinfunction "2_2") (pintype "passive"))
      (node (ref "C17") (pin "2") (pinfunction "2_2") (pintype "passive"))
      (node (ref "C18") (pin "2") (pinfunction "2_2") (pintype "passive"))
      (node (ref "C19") (pin "2") (pinfunction "2_2") (pintype "passive"))
      (node (ref "C20") (pin "2") (pinfunction "2_2") (pintype "passive"))
      (node (ref "C21") (pin "2") (pinfunction "2_2") (pintype "passive"))
      (node (ref "C22") (pin "2") (pinfunction "2_2") (pintype "passive"))
      (node (ref "C23") (pin "2") (pinfunction "2_2") (pintype "passive"))
      (node (ref "C24") (pin "2") (pinfunction "2_2") (pintype "passive"))
      (node (ref "C25") (pin "2") (pinfunction "2_2") (pintype "passive"))
      (node (ref "C26") (pin "2") (pinfunction "2_2") (pintype "passive"))
      (node (ref "C27") (pin "2") (pinfunction "2_2") (pintype "passive"))
      (node (ref "C28") (pin "2") (pinfunction "2_2") (pintype "passive"))
      (node (ref "C29") (pin "2") (pinfunction "2_2") (pintype "passive"))
      (node (ref "C3") (pin "2") (pinfunction "2_2") (pintype "passive"))
      (node (ref "C30") (pin "2") (pinfunction "2_2") (pintype "passive"))
      (node (ref "C4") (pin "2") (pinfunction "2_2") (pintype "passive"))
      (node (ref "C5") (pin "2") (pinfunction "2_2") (pintype "passive"))
      (node (ref "C6") (pin "2") (pinfunction "2_2") (pintype "passive"))
      (node (ref "C7") (pin "2") (pinfunction "2_2") (pintype "passive"))
      (node (ref "C8") (pin "2") (pinfunction "2_2") (pintype "passive"))
      (node (ref "C9") (pin "2") (pinfunction "2_2") (pintype "passive"))
      (node (ref "J1") (pin "1") (pinfunction "1_1") (pintype "passive"))
      (node (ref "J1") (pin "9") (pinfunction "9_9") (pintype "passive"))
      (node (ref "R11") (pin "2") (pinfunction "2_2") (pintype "passive"))
      (node (ref "R15") (pin "2") (pinfunction "2_2") (pintype "passive"))
      (node (ref "R16") (pin "2") (pinfunction "2_2") (pintype "passive"))
      (node (ref "R24") (pin "2") (pinfunction "2_2") (pintype "passive"))
      (node (ref "R25") (pin "2") (pinfunction "2_2") (pintype "passive"))
      (node (ref "R26") (pin "2") (pinfunction "2_2") (pintype "passive"))
      (node (ref "R6") (pin "1") (pinfunction "1_1") (pintype "passive"))
      (node (ref "R7") (pin "1") (pinfunction "1_1") (pintype "passive"))
      (node (ref "U1") (pin "4") (pinfunction "GND_4") (pintype "power_in"))
      (node (ref "U2") (pin "29") (pinfunction "GND_29") (pintype "power_in"))
      (node (ref "U2") (pin "30") (pinfunction "GND_30") (pintype "power_in"))
      (node (ref "U2") (pin "65") (pinfunction "GND_65") (pintype "power_in"))
      (node (ref "Y2") (pin "2") (pinfunction "GND_2") (pintype "power_in"))
      (node (ref "Y3") (pin "2") (pinfunction "GND_2") (pintype "power_in"))
      (node (ref "Y3") (pin "4") (pinfunction "GND_4") (pintype "power_in"))
    )
    (net (code "45") (name "MCU_RESET_IN") (class "Default")
      (node (ref "R12") (pin "2") (pinfunction "2_2") (pintype "passive"))
    )
    (net (code "46") (name "Net-(C28-Pad1)") (class "Default")
      (node (ref "C28") (pin "1") (pinfunction "1_1") (pintype "passive"))
      (node (ref "R17") (pin "1") (pinfunction "1_1") (pintype "passive"))
      (node (ref "Y3") (pin "1") (pinfunction "1_1") (pintype "passive"))
    )
    (net (code "47") (name "Net-(J1-Pad2)") (class "Default")
      (node (ref "J1") (pin "2") (pinfunction "2_2") (pintype "passive"))
      (node (ref "R12") (pin "1") (pinfunction "1_1") (pintype "passive"))
    )
    (net (code "48") (name "Net-(J1-Pad5)") (class "Default")
      (node (ref "J1") (pin "5") (pinfunction "5_5") (pintype "passive"))
      (node (ref "R13") (pin "2") (pinfunction "2_2") (pintype "passive"))
    )
    (net (code "49") (name "Net-(J2-Pad2)") (class "Default")
      (node (ref "J2") (pin "2") (pinfunction "2_2") (pintype "passive"))
      (node (ref "R21") (pin "1") (pinfunction "1_1") (pintype "passive"))
      (node (ref "R22") (pin "1") (pinfunction "1_1") (pintype "passive"))
      (node (ref "R23") (pin "1") (pinfunction "1_1") (pintype "passive"))
    )
    (net (code "50") (name "Net-(J3-Pad1)") (class "Default")
      (node (ref "J3") (pin "1") (pinfunction "1_1") (pintype "passive"))
      (node (ref "R21") (pin "2") (pinfunction "2_2") (pintype "passive"))
    )
    (net (code "51") (name "Net-(J3-Pad3)") (class "Default")
      (node (ref "J3") (pin "3") (pinfunction "3_3") (pintype "passive"))
      (node (ref "R24") (pin "1") (pinfunction "1_1") (pintype "passive"))
    )
    (net (code "52") (name "Net-(J4-Pad1)") (class "Default")
      (node (ref "J4") (pin "1") (pinfunction "1_1") (pintype "passive"))
      (node (ref "R22") (pin "2") (pinfunction "2_2") (pintype "passive"))
    )
    (net (code "53") (name "Net-(J4-Pad3)") (class "Default")
      (node (ref "J4") (pin "3") (pinfunction "3_3") (pintype "passive"))
      (node (ref "R25") (pin "1") (pinfunction "1_1") (pintype "passive"))
    )
    (net (code "54") (name "Net-(J5-Pad1)") (class "Default")
      (node (ref "J5") (pin "1") (pinfunction "1_1") (pintype "passive"))
      (node (ref "R23") (pin "2") (pinfunction "2_2") (pintype "passive"))
    )
    (net (code "55") (name "Net-(J5-Pad3)") (class "Default")
      (node (ref "J5") (pin "3") (pinfunction "3_3") (pintype "passive"))
      (node (ref "R26") (pin "1") (pinfunction "1_1") (pintype "passive"))
    )
    (net (code "56") (name "Net-(U1-VCC)") (class "Default")
      (node (ref "C1") (pin "1") (pinfunction "1_1") (pintype "passive"))
      (node (ref "R3") (pin "1") (pinfunction "1_1") (pintype "passive"))
      (node (ref "R4") (pin "1") (pinfunction "1_1") (pintype "passive"))
      (node (ref "R5") (pin "1") (pinfunction "1_1") (pintype "passive"))
      (node (ref "U1") (pin "8") (pinfunction "VCC_8") (pintype "power_in"))
    )
    (net (code "57") (name "Net-(U1-~{RESET}{slash}SIO3)") (class "Default")
      (node (ref "R3") (pin "2") (pinfunction "2_2") (pintype "passive"))
      (node (ref "U1") (pin "3") (pinfunction "~{WP}/SIO2_3") (pintype "bidirectional"))
      (node (ref "U1") (pin "7") (pinfunction "~{RESET}/SIO3_7") (pintype "bidirectional"))
    )
    (net (code "58") (name "Net-(U2-DCDC_ANA_SW)") (class "Default")
      (node (ref "L1") (pin "2") (pinfunction "2_2") (pintype "passive"))
      (node (ref "U2") (pin "38") (pinfunction "DCDC_ANA_SW_38") (pintype "power_in"))
    )
    (net (code "59") (name "Net-(U2-DCDC_DIG_SW)") (class "Default")
      (node (ref "L4") (pin "2") (pinfunction "2_2") (pintype "passive"))
      (node (ref "U2") (pin "43") (pinfunction "DCDC_DIG_SW_43") (pintype "power_in"))
    )
    (net (code "60") (name "Net-(Y1-OSC1)") (class "Default")
      (node (ref "C26") (pin "1") (pinfunction "1_1") (pintype "passive"))
      (node (ref "R18") (pin "1") (pinfunction "1_1") (pintype "passive"))
      (node (ref "Y1") (pin "1") (pinfunction "OSC1_1") (pintype "passive"))
    )
    (net (code "61") (name "Net-(Y2-CLKOE)") (class "Default")
      (node (ref "R19") (pin "2") (pinfunction "2_2") (pintype "passive"))
      (node (ref "Y2") (pin "3") (pinfunction "CLKOE_3") (pintype "input"))
    )
    (net (code "62") (name "Net-(Y2-CLKOUT)") (class "Default")
      (node (ref "R20") (pin "1") (pinfunction "1_1") (pintype "passive"))
      (node (ref "Y2") (pin "1") (pinfunction "CLKOUT_1") (pintype "output"))
    )
    (net (code "63") (name "SOP0") (class "Default")
      (node (ref "C29") (pin "1") (pinfunction "1_1") (pintype "passive"))
      (node (ref "J5") (pin "2") (pinfunction "2_2") (pintype "passive"))
      (node (ref "U2") (pin "35") (pinfunction "SOP0_35") (pintype "passive"))
    )
    (net (code "64") (name "SOP1") (class "Default")
      (node (ref "J4") (pin "2") (pinfunction "2_2") (pintype "passive"))
      (node (ref "U2") (pin "34") (pinfunction "SOP1_34") (pintype "passive"))
    )
    (net (code "65") (name "VBAT_CC") (class "Default")
      (node (ref "C12") (pin "1") (pinfunction "1_1") (pintype "passive"))
      (node (ref "C13") (pin "1") (pinfunction "1_1") (pintype "passive"))
      (node (ref "C14") (pin "1") (pinfunction "1_1") (pintype "passive"))
      (node (ref "C5") (pin "1") (pinfunction "1_1") (pintype "passive"))
      (node (ref "C6") (pin "1") (pinfunction "1_1") (pintype "passive"))
      (node (ref "J2") (pin "1") (pinfunction "1_1") (pintype "passive"))
      (node (ref "R1") (pin "2") (pinfunction "2_2") (pintype "passive"))
      (node (ref "R10") (pin "2") (pinfunction "2_2") (pintype "passive"))
      (node (ref "R14") (pin "1") (pinfunction "1_1") (pintype "passive"))
      (node (ref "R4") (pin "2") (pinfunction "2_2") (pintype "passive"))
      (node (ref "R8") (pin "1") (pinfunction "1_1") (pintype "passive"))
      (node (ref "R9") (pin "1") (pinfunction "1_1") (pintype "passive"))
      (node (ref "U2") (pin "37") (pinfunction "VIN_DCDC_ANA_37") (pintype "power_in"))
      (node (ref "U2") (pin "39") (pinfunction "VIN_DCDC_PA_39") (pintype "power_in"))
      (node (ref "U2") (pin "44") (pinfunction "VIN_DCDC_DIG_44") (pintype "power_in"))
    )
    (net (code "66") (name "VCC_BRD") (class "Default")
      (node (ref "C25") (pin "1") (pinfunction "1_1") (pintype "passive"))
      (node (ref "J2") (pin "3") (pinfunction "3_3") (pintype "passive"))
      (node (ref "R19") (pin "1") (pinfunction "1_1") (pintype "passive"))
      (node (ref "R27") (pin "1") (pinfunction "1_1") (pintype "passive"))
      (node (ref "Y2") (pin "4") (pinfunction "VDD_4") (pintype "power_in"))
    )
    (net (code "67") (name "VCC_LDO_3V3") (class "Default")
      (node (ref "R2") (pin "2") (pinfunction "2_2") (pintype "passive"))
    )
    (net (code "68") (name "VCC_MCU_5V") (class "Default")
      (node (ref "R13") (pin "1") (pinfunction "1_1") (pintype "passive"))
    )
    (net (code "69") (name "unconnected-(J1-Pad3)") (class "Default")
      (node (ref "J1") (pin "3") (pinfunction "3_3") (pintype "passive+no_connect"))
    )
    (net (code "70") (name "unconnected-(J1-Pad4)") (class "Default")
      (node (ref "J1") (pin "4") (pinfunction "4_4") (pintype "passive+no_connect"))
    )
    (net (code "71") (name "unconnected-(U2-DIO23-Pad16)") (class "Default")
      (node (ref "U2") (pin "16") (pinfunction "DIO23_16") (pintype "bidirectional+no_connect"))
    )
    (net (code "72") (name "unconnected-(U2-DIO24-Pad17)") (class "Default")
      (node (ref "U2") (pin "17") (pinfunction "DIO24_17") (pintype "bidirectional+no_connect"))
    )
    (net (code "73") (name "unconnected-(U2-DIO29-Pad20)") (class "Default")
      (node (ref "U2") (pin "20") (pinfunction "DIO29_20") (pintype "bidirectional+no_connect"))
    )
    (net (code "74") (name "unconnected-(U2-DIO31-Pad45)") (class "Default")
      (node (ref "U2") (pin "45") (pinfunction "DIO31_45") (pintype "bidirectional+no_connect"))
    )
    (net (code "75") (name "unconnected-(U2-NC-Pad26)") (class "Default")
      (node (ref "U2") (pin "26") (pinfunction "NC_26") (pintype "passive+no_connect"))
    )
    (net (code "76") (name "unconnected-(U2-NC-Pad46)") (class "Default")
      (node (ref "U2") (pin "46") (pinfunction "NC_46") (pintype "passive+no_connect"))
    )
    (net (code "77") (name "unconnected-(U2-Reserved-Pad19)") (class "Default")
      (node (ref "U2") (pin "19") (pinfunction "Reserved_19") (pintype "passive+no_connect"))
    )
  )
)
